# zeta2rework_lw_v7.net
KiCad netlist of a schematic drawn in EAGLE
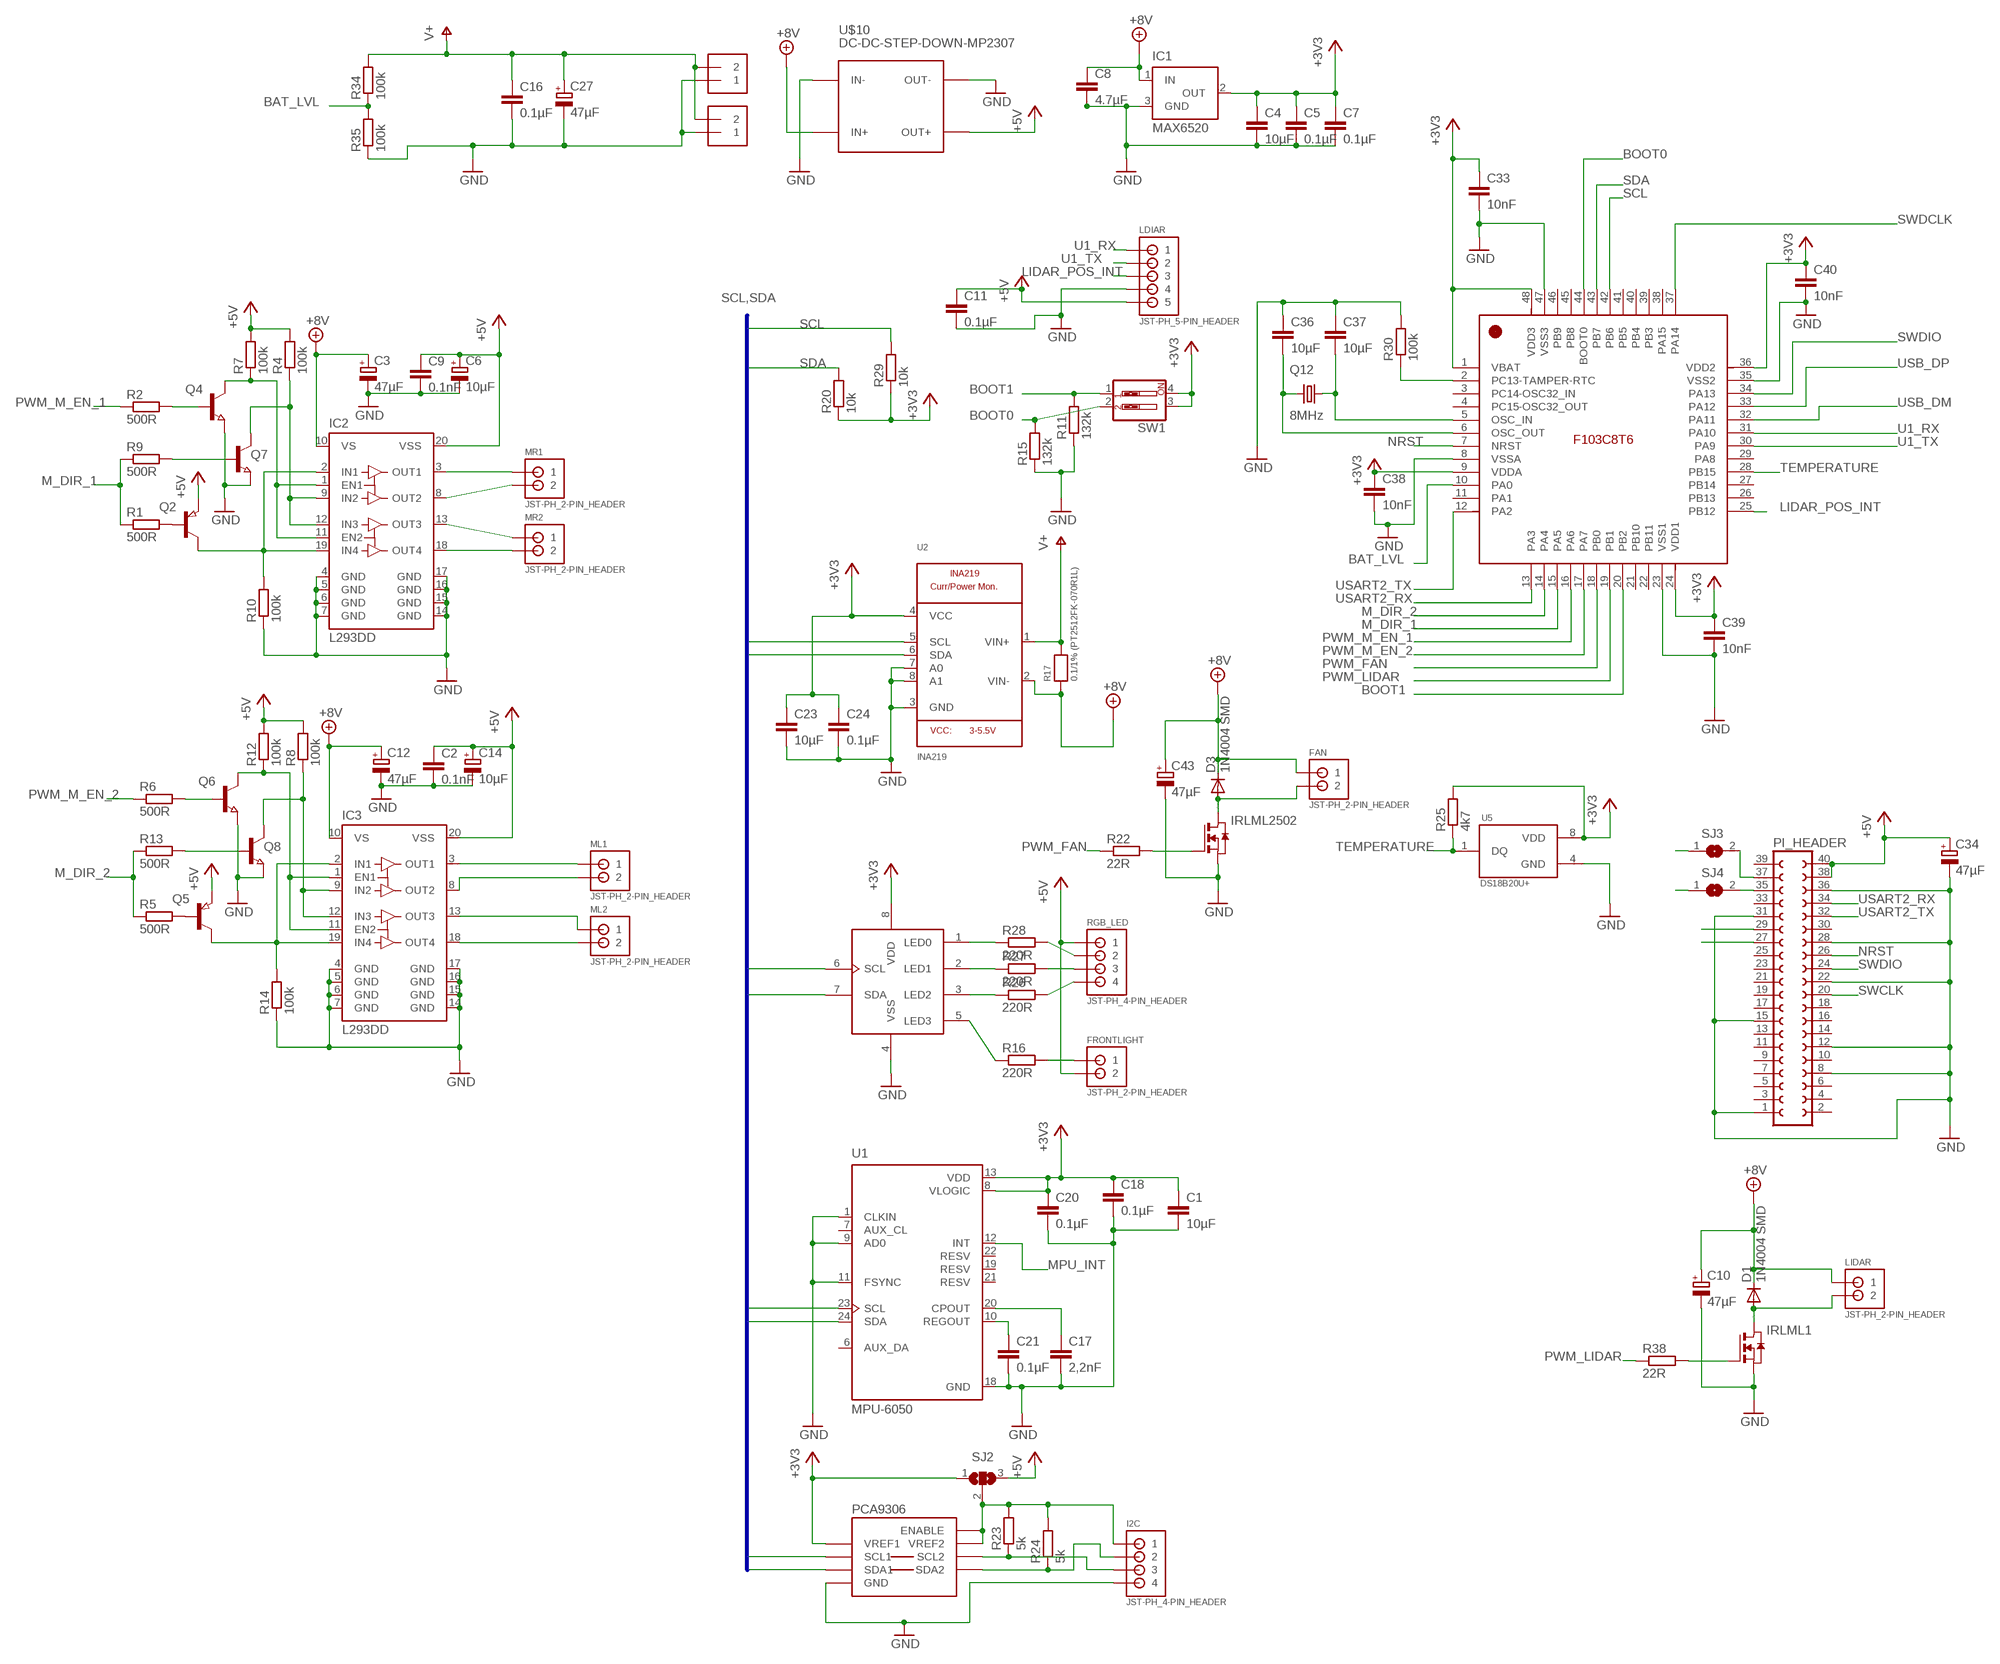
[diagram p0: schematic, sheet 1]

(export (version "E")
  (design (tool "Eeschema 10.0.6"))
  (components
    (comp (ref "C1")
      (value "10µF")
      (footprint "eagle-import:C1206")
      (libsource (lib "eagle-import") (part "C-EUC1206"))
    )
    (comp (ref "C2")
      (value "0.1nF")
      (footprint "eagle-import:C1206")
      (libsource (lib "eagle-import") (part "C-EUC1206"))
    )
    (comp (ref "C3")
      (value "47µF")
      (footprint "eagle-import:UD-4X5,8_NICHICON")
      (libsource (lib "eagle-import") (part "CPOL-EUUD-4X5,8"))
    )
    (comp (ref "C4")
      (value "10µF")
      (footprint "eagle-import:C1206")
      (libsource (lib "eagle-import") (part "C-EUC1206"))
    )
    (comp (ref "C5")
      (value "0.1µF")
      (footprint "eagle-import:C1206")
      (libsource (lib "eagle-import") (part "C-EUC1206"))
    )
    (comp (ref "C6")
      (value "10µF")
      (footprint "eagle-import:UD-4X5,8_NICHICON")
      (libsource (lib "eagle-import") (part "CPOL-EUUD-4X5,8"))
    )
    (comp (ref "C7")
      (value "0.1µF")
      (footprint "eagle-import:C1206")
      (libsource (lib "eagle-import") (part "C-EUC1206"))
    )
    (comp (ref "C8")
      (value "4.7µF")
      (footprint "eagle-import:C1206")
      (libsource (lib "eagle-import") (part "C-EUC1206"))
    )
    (comp (ref "C9")
      (value "0.1nF")
      (footprint "eagle-import:C1206")
      (libsource (lib "eagle-import") (part "C-EUC1206"))
    )
    (comp (ref "C10")
      (value "47µF")
      (footprint "eagle-import:UD-4X5,8_NICHICON")
      (libsource (lib "eagle-import") (part "CPOL-EUUD-4X5,8"))
    )
    (comp (ref "C11")
      (value "0.1µF")
      (footprint "eagle-import:C1206")
      (libsource (lib "eagle-import") (part "C-EUC1206"))
    )
    (comp (ref "C12")
      (value "47µF")
      (footprint "eagle-import:UD-4X5,8_NICHICON")
      (libsource (lib "eagle-import") (part "CPOL-EUUD-4X5,8"))
    )
    (comp (ref "C14")
      (value "10µF")
      (footprint "eagle-import:UD-4X5,8_NICHICON")
      (libsource (lib "eagle-import") (part "CPOL-EUUD-4X5,8"))
    )
    (comp (ref "C16")
      (value "0.1µF")
      (footprint "eagle-import:C1206")
      (libsource (lib "eagle-import") (part "C-EUC1206"))
    )
    (comp (ref "C17")
      (value "2,2nF")
      (footprint "eagle-import:C1206")
      (libsource (lib "eagle-import") (part "C-EUC1206"))
    )
    (comp (ref "C18")
      (value "0.1µF")
      (footprint "eagle-import:C1206")
      (libsource (lib "eagle-import") (part "C-EUC1206"))
    )
    (comp (ref "C20")
      (value "0.1µF")
      (footprint "eagle-import:C1206")
      (libsource (lib "eagle-import") (part "C-EUC1206"))
    )
    (comp (ref "C21")
      (value "0.1µF")
      (footprint "eagle-import:C1206")
      (libsource (lib "eagle-import") (part "C-EUC1206"))
    )
    (comp (ref "C23")
      (value "10µF")
      (footprint "eagle-import:C1206")
      (libsource (lib "eagle-import") (part "C-EUC1206"))
    )
    (comp (ref "C24")
      (value "0.1µF")
      (footprint "eagle-import:C1206")
      (libsource (lib "eagle-import") (part "C-EUC1206"))
    )
    (comp (ref "C27")
      (value "47µF")
      (footprint "eagle-import:UD-4X5,8_NICHICON")
      (libsource (lib "eagle-import") (part "CPOL-EUUD-4X5,8"))
    )
    (comp (ref "C33")
      (value "10nF")
      (footprint "eagle-import:C1206")
      (libsource (lib "eagle-import") (part "C-EUC1206"))
    )
    (comp (ref "C34")
      (value "47µF")
      (footprint "eagle-import:UD-4X5,8_NICHICON")
      (libsource (lib "eagle-import") (part "CPOL-EUUD-4X5,8"))
    )
    (comp (ref "C36")
      (value "10µF")
      (footprint "eagle-import:C1206")
      (libsource (lib "eagle-import") (part "C-EUC1206"))
    )
    (comp (ref "C37")
      (value "10µF")
      (footprint "eagle-import:C1206")
      (libsource (lib "eagle-import") (part "C-EUC1206"))
    )
    (comp (ref "C38")
      (value "10nF")
      (footprint "eagle-import:C1206")
      (libsource (lib "eagle-import") (part "C-EUC1206"))
    )
    (comp (ref "C39")
      (value "10nF")
      (footprint "eagle-import:C1206")
      (libsource (lib "eagle-import") (part "C-EUC1206"))
    )
    (comp (ref "C40")
      (value "10nF")
      (footprint "eagle-import:C1206")
      (libsource (lib "eagle-import") (part "C-EUC1206"))
    )
    (comp (ref "C43")
      (value "47µF")
      (footprint "eagle-import:UD-4X5,8_NICHICON")
      (libsource (lib "eagle-import") (part "CPOL-EUUD-4X5,8"))
    )
    (comp (ref "D1")
      (value "1N4004 SMD")
      (footprint "eagle-import:DO214AC")
      (libsource (lib "eagle-import") (part "DIODE-DO214AC"))
    )
    (comp (ref "D3")
      (value "1N4004 SMD")
      (footprint "eagle-import:DO214AC")
      (libsource (lib "eagle-import") (part "DIODE-DO214AC"))
    )
    (comp (ref "FAN")
      (value "JST-PH_2-PIN_HEADER")
      (footprint "eagle-import:JST_B2B-PH_HEADER")
      (libsource (lib "eagle-import") (part "JST-PH_2-PIN_HEADER"))
    )
    (comp (ref "FRONTLIGHT")
      (value "JST-PH_2-PIN_HEADER")
      (footprint "eagle-import:JST_B2B-PH_HEADER")
      (libsource (lib "eagle-import") (part "JST-PH_2-PIN_HEADER"))
    )
    (comp (ref "I2C")
      (value "JST-PH_4-PIN_HEADER")
      (footprint "eagle-import:JST_B4B-PH_HEADER")
      (libsource (lib "eagle-import") (part "JST-PH_4-PIN_HEADER"))
    )
    (comp (ref "IC1")
      (value "MAX6520")
      (footprint "eagle-import:SOT23")
      (fields (field (name "MF") "MAXIM") (field (name "MPN") "MAX6520EUR-T"))
      (libsource (lib "eagle-import") (part "MAX6520"))
    )
    (comp (ref "IC2")
      (value "L293DD")
      (footprint "eagle-import:SO20")
      (libsource (lib "eagle-import") (part "L293DD"))
    )
    (comp (ref "IC3")
      (value "L293DD")
      (footprint "eagle-import:SO20")
      (libsource (lib "eagle-import") (part "L293DD"))
    )
    (comp (ref "IRLML1")
      (value "NMOSSOT23")
      (footprint "eagle-import:SOT-23")
      (libsource (lib "eagle-import") (part "NMOSSOT23"))
    )
    (comp (ref "IRLML2502")
      (value "NMOSSOT23")
      (footprint "eagle-import:SOT-23")
      (libsource (lib "eagle-import") (part "NMOSSOT23"))
    )
    (comp (ref "LDIAR")
      (value "JST-PH_5-PIN_HEADER")
      (footprint "eagle-import:JST_B5B-PH_HEADER")
      (libsource (lib "eagle-import") (part "JST-PH_5-PIN_HEADER"))
    )
    (comp (ref "LIDAR")
      (value "JST-PH_2-PIN_HEADER")
      (footprint "eagle-import:JST_B2B-PH_HEADER")
      (libsource (lib "eagle-import") (part "JST-PH_2-PIN_HEADER"))
    )
    (comp (ref "ML1")
      (value "JST-PH_2-PIN_HEADER")
      (footprint "eagle-import:JST_B2B-PH_HEADER")
      (libsource (lib "eagle-import") (part "JST-PH_2-PIN_HEADER"))
    )
    (comp (ref "ML2")
      (value "JST-PH_2-PIN_HEADER")
      (footprint "eagle-import:JST_B2B-PH_HEADER")
      (libsource (lib "eagle-import") (part "JST-PH_2-PIN_HEADER"))
    )
    (comp (ref "MR1")
      (value "JST-PH_2-PIN_HEADER")
      (footprint "eagle-import:JST_B2B-PH_HEADER")
      (libsource (lib "eagle-import") (part "JST-PH_2-PIN_HEADER"))
    )
    (comp (ref "MR2")
      (value "JST-PH_2-PIN_HEADER")
      (footprint "eagle-import:JST_B2B-PH_HEADER")
      (libsource (lib "eagle-import") (part "JST-PH_2-PIN_HEADER"))
    )
    (comp (ref "PCA9306")
      (value "IC2_LEVEL_TRANSLATER")
      (footprint "eagle-import:SOIC-8")
      (libsource (lib "eagle-import") (part "IC2_LEVEL_TRANSLATER"))
    )
    (comp (ref "PCA9533")
      (value "PCA9533")
      (footprint "eagle-import:SOIC8")
      (libsource (lib "eagle-import") (part "PCA9533"))
    )
    (comp (ref "PI_HEADER")
      (value "FE20-2")
      (footprint "eagle-import:FE20-2")
      (libsource (lib "eagle-import") (part "FE20-2"))
    )
    (comp (ref "Q2")
      (value "PNP-TRANSISTOR_SOT23")
      (footprint "eagle-import:SOT23")
      (libsource (lib "eagle-import") (part "PNP-TRANSISTOR_SOT23"))
    )
    (comp (ref "Q4")
      (value "NPN-TRANSISTOR_SOT23")
      (footprint "eagle-import:SOT23")
      (libsource (lib "eagle-import") (part "NPN-TRANSISTOR_SOT23"))
    )
    (comp (ref "Q5")
      (value "PNP-TRANSISTOR_SOT23")
      (footprint "eagle-import:SOT23")
      (libsource (lib "eagle-import") (part "PNP-TRANSISTOR_SOT23"))
    )
    (comp (ref "Q6")
      (value "NPN-TRANSISTOR_SOT23")
      (footprint "eagle-import:SOT23")
      (libsource (lib "eagle-import") (part "NPN-TRANSISTOR_SOT23"))
    )
    (comp (ref "Q7")
      (value "NPN-TRANSISTOR_SOT23")
      (footprint "eagle-import:SOT23")
      (libsource (lib "eagle-import") (part "NPN-TRANSISTOR_SOT23"))
    )
    (comp (ref "Q8")
      (value "NPN-TRANSISTOR_SOT23")
      (footprint "eagle-import:SOT23")
      (libsource (lib "eagle-import") (part "NPN-TRANSISTOR_SOT23"))
    )
    (comp (ref "Q12")
      (value "8MHz")
      (footprint "eagle-import:7.0X5.0")
      (libsource (lib "eagle-import") (part "KX-13"))
    )
    (comp (ref "R1")
      (value "500R")
      (footprint "eagle-import:R0603")
      (libsource (lib "eagle-import") (part "R-EU_R0603"))
    )
    (comp (ref "R2")
      (value "500R")
      (footprint "eagle-import:R0603")
      (libsource (lib "eagle-import") (part "R-EU_R0603"))
    )
    (comp (ref "R4")
      (value "100k")
      (footprint "eagle-import:R0603")
      (libsource (lib "eagle-import") (part "R-EU_R0603"))
    )
    (comp (ref "R5")
      (value "500R")
      (footprint "eagle-import:R0603")
      (libsource (lib "eagle-import") (part "R-EU_R0603"))
    )
    (comp (ref "R6")
      (value "500R")
      (footprint "eagle-import:R0603")
      (libsource (lib "eagle-import") (part "R-EU_R0603"))
    )
    (comp (ref "R7")
      (value "100k")
      (footprint "eagle-import:R0603")
      (libsource (lib "eagle-import") (part "R-EU_R0603"))
    )
    (comp (ref "R8")
      (value "100k")
      (footprint "eagle-import:R0603")
      (libsource (lib "eagle-import") (part "R-EU_R0603"))
    )
    (comp (ref "R9")
      (value "500R")
      (footprint "eagle-import:R0603")
      (libsource (lib "eagle-import") (part "R-EU_R0603"))
    )
    (comp (ref "R10")
      (value "100k")
      (footprint "eagle-import:R0603")
      (libsource (lib "eagle-import") (part "R-EU_R0603"))
    )
    (comp (ref "R11")
      (value "132k")
      (footprint "eagle-import:R0603")
      (libsource (lib "eagle-import") (part "R-EU_R0603"))
    )
    (comp (ref "R12")
      (value "100k")
      (footprint "eagle-import:R0603")
      (libsource (lib "eagle-import") (part "R-EU_R0603"))
    )
    (comp (ref "R13")
      (value "500R")
      (footprint "eagle-import:R0603")
      (libsource (lib "eagle-import") (part "R-EU_R0603"))
    )
    (comp (ref "R14")
      (value "100k")
      (footprint "eagle-import:R0603")
      (libsource (lib "eagle-import") (part "R-EU_R0603"))
    )
    (comp (ref "R15")
      (value "132k")
      (footprint "eagle-import:R0603")
      (libsource (lib "eagle-import") (part "R-EU_R0603"))
    )
    (comp (ref "R16")
      (value "220R")
      (footprint "eagle-import:R0603")
      (libsource (lib "eagle-import") (part "R-EU_R0603"))
    )
    (comp (ref "R17")
      (value "0.1/1% (PT2512FK-070R1L)")
      (footprint "eagle-import:2512")
      (libsource (lib "eagle-import") (part "RESISTOR2512"))
    )
    (comp (ref "R20")
      (value "10k")
      (footprint "eagle-import:R0603")
      (libsource (lib "eagle-import") (part "R-EU_R0603"))
    )
    (comp (ref "R22")
      (value "22R")
      (footprint "eagle-import:R0603")
      (libsource (lib "eagle-import") (part "R-EU_R0603"))
    )
    (comp (ref "R23")
      (value "5k")
      (footprint "eagle-import:R0603")
      (libsource (lib "eagle-import") (part "R-EU_R0603"))
    )
    (comp (ref "R24")
      (value "5k")
      (footprint "eagle-import:R0603")
      (libsource (lib "eagle-import") (part "R-EU_R0603"))
    )
    (comp (ref "R25")
      (value "4k7")
      (footprint "eagle-import:R0603")
      (libsource (lib "eagle-import") (part "R-EU_R0603"))
    )
    (comp (ref "R26")
      (value "220R")
      (footprint "eagle-import:R0603")
      (libsource (lib "eagle-import") (part "R-EU_R0603"))
    )
    (comp (ref "R27")
      (value "220R")
      (footprint "eagle-import:R0603")
      (libsource (lib "eagle-import") (part "R-EU_R0603"))
    )
    (comp (ref "R28")
      (value "220R")
      (footprint "eagle-import:R0603")
      (libsource (lib "eagle-import") (part "R-EU_R0603"))
    )
    (comp (ref "R29")
      (value "10k")
      (footprint "eagle-import:R0603")
      (libsource (lib "eagle-import") (part "R-EU_R0603"))
    )
    (comp (ref "R30")
      (value "100k")
      (footprint "eagle-import:R0603")
      (libsource (lib "eagle-import") (part "R-EU_R0603"))
    )
    (comp (ref "R34")
      (value "100k")
      (footprint "eagle-import:R0603")
      (libsource (lib "eagle-import") (part "R-EU_R0603"))
    )
    (comp (ref "R35")
      (value "100k")
      (footprint "eagle-import:R0603")
      (libsource (lib "eagle-import") (part "R-EU_R0603"))
    )
    (comp (ref "R38")
      (value "22R")
      (footprint "eagle-import:R0603")
      (libsource (lib "eagle-import") (part "R-EU_R0603"))
    )
    (comp (ref "RGB_LED")
      (value "JST-PH_4-PIN_HEADER")
      (footprint "eagle-import:JST_B4B-PH_HEADER")
      (libsource (lib "eagle-import") (part "JST-PH_4-PIN_HEADER"))
    )
    (comp (ref "SJ2")
      (value "SJ2W")
      (footprint "eagle-import:SJ_2")
      (libsource (lib "eagle-import") (part "SJ2W"))
    )
    (comp (ref "SJ3")
      (value "SOLDERJUMPERREFLOW_NOPASTE")
      (footprint "eagle-import:SOLDERJUMPER_REFLOW_NOPASTE")
      (libsource (lib "eagle-import") (part "SOLDERJUMPERREFLOW_NOPASTE"))
    )
    (comp (ref "SJ4")
      (value "SOLDERJUMPERREFLOW_NOPASTE")
      (footprint "eagle-import:SOLDERJUMPER_REFLOW_NOPASTE")
      (libsource (lib "eagle-import") (part "SOLDERJUMPERREFLOW_NOPASTE"))
    )
    (comp (ref "STM32F103CB")
      (value "STM32F103CB")
      (footprint "eagle-import:LQFP48_7X7MM_0.5MMPP")
      (fields (field (name "MF") "STMicroelectronics") (field (name "MP") "STM32F103C8T6"))
      (libsource (lib "eagle-import") (part "STM32F103C8T6"))
    )
    (comp (ref "SUPPLY_IN")
      (value "TERMBLOCK_1X2-3.5MM")
      (footprint "eagle-import:1X2-3.5MM")
      (libsource (lib "eagle-import") (part "TERMBLOCK_1X2-3.5MM"))
    )
    (comp (ref "SUPPLY_IN1")
      (value "TERMBLOCK_1X2-3.5MM")
      (footprint "eagle-import:1X2-3.5MM")
      (libsource (lib "eagle-import") (part "TERMBLOCK_1X2-3.5MM"))
    )
    (comp (ref "SW1")
      (value "SW_DIP-2")
      (footprint "eagle-import:EDG-02")
      (libsource (lib "eagle-import") (part "SW_DIP-2"))
    )
    (comp (ref "U$10")
      (value "DC-DC-STEP-DOWN-MP2307")
      (footprint "eagle-import:DC-DC-STEP-DOWN-MP2307")
      (libsource (lib "eagle-import") (part "DC-DC-STEP-DOWN-MP2307"))
    )
    (comp (ref "U1")
      (value "MPU-6050")
      (footprint "eagle-import:QFN50P400X400X95-24N")
      (fields (field (name "MF") "TDK"))
      (libsource (lib "eagle-import") (part "MPU-6050"))
    )
    (comp (ref "U2")
      (value "INA219")
      (footprint "eagle-import:SOT23-8")
      (fields (field (name "MF") "Texas Instruments"))
      (libsource (lib "eagle-import") (part "INA219"))
    )
    (comp (ref "U5")
      (value "DS18B20U+")
      (footprint "eagle-import:SOP65P490X95-8N")
      (fields (field (name "MF") "Maxim"))
      (libsource (lib "eagle-import") (part "DS18B20U+"))
    )
  )
  (nets
    (net (code "1") (name "+3V3") (class "Default")
      (node (ref "C1") (pin "1") (pinfunction "1_1") (pintype "passive"))
      (node (ref "C18") (pin "1") (pinfunction "1_1") (pintype "passive"))
      (node (ref "C20") (pin "1") (pinfunction "1_1") (pintype "passive"))
      (node (ref "C23") (pin "1") (pinfunction "1_1") (pintype "passive"))
      (node (ref "C24") (pin "1") (pinfunction "1_1") (pintype "passive"))
      (node (ref "C33") (pin "1") (pinfunction "1_1") (pintype "passive"))
      (node (ref "C38") (pin "1") (pinfunction "1_1") (pintype "passive"))
      (node (ref "C39") (pin "1") (pinfunction "1_1") (pintype "passive"))
      (node (ref "C4") (pin "1") (pinfunction "1_1") (pintype "passive"))
      (node (ref "C40") (pin "1") (pinfunction "1_1") (pintype "passive"))
      (node (ref "C5") (pin "1") (pinfunction "1_1") (pintype "passive"))
      (node (ref "C7") (pin "1") (pinfunction "1_1") (pintype "passive"))
      (node (ref "IC1") (pin "2") (pinfunction "OUT_2") (pintype "output"))
      (node (ref "PCA9306") (pin "1") (pinfunction "VREF1_1") (pintype "power_in"))
      (node (ref "PCA9533") (pin "8") (pinfunction "VDD_8") (pintype "power_in"))
      (node (ref "R20") (pin "1") (pinfunction "1_1") (pintype "passive"))
      (node (ref "R25") (pin "2") (pinfunction "2_2") (pintype "passive"))
      (node (ref "R29") (pin "1") (pinfunction "1_1") (pintype "passive"))
      (node (ref "SJ2") (pin "1") (pinfunction "1_1") (pintype "passive"))
      (node (ref "STM32F103CB") (pin "1") (pinfunction "VBAT_1") (pintype "bidirectional"))
      (node (ref "STM32F103CB") (pin "24") (pinfunction "VDD1_24") (pintype "bidirectional"))
      (node (ref "STM32F103CB") (pin "36") (pinfunction "VDD2_36") (pintype "bidirectional"))
      (node (ref "STM32F103CB") (pin "48") (pinfunction "VDD3_48") (pintype "bidirectional"))
      (node (ref "STM32F103CB") (pin "9") (pinfunction "VDDA_9") (pintype "bidirectional"))
      (node (ref "SW1") (pin "3") (pinfunction "3_3") (pintype "passive"))
      (node (ref "SW1") (pin "4") (pinfunction "4_4") (pintype "passive"))
      (node (ref "U1") (pin "13") (pinfunction "VDD_13") (pintype "power_in"))
      (node (ref "U1") (pin "8") (pinfunction "VLOGIC_8") (pintype "power_in"))
      (node (ref "U2") (pin "4") (pinfunction "VCC_4") (pintype "bidirectional"))
      (node (ref "U5") (pin "8") (pinfunction "VDD_8") (pintype "power_in"))
    )
    (net (code "2") (name "+5V") (class "Default")
      (node (ref "C11") (pin "1") (pinfunction "1_1") (pintype "passive"))
      (node (ref "C14") (pin "+") (pinfunction "+_+") (pintype "passive"))
      (node (ref "C2") (pin "1") (pinfunction "1_1") (pintype "passive"))
      (node (ref "C34") (pin "+") (pinfunction "+_+") (pintype "passive"))
      (node (ref "C6") (pin "+") (pinfunction "+_+") (pintype "passive"))
      (node (ref "C9") (pin "1") (pinfunction "1_1") (pintype "passive"))
      (node (ref "FRONTLIGHT") (pin "P2") (pinfunction "2_P2") (pintype "bidirectional"))
      (node (ref "IC2") (pin "20") (pinfunction "VSS_20") (pintype "power_in"))
      (node (ref "IC3") (pin "20") (pinfunction "VSS_20") (pintype "power_in"))
      (node (ref "LDIAR") (pin "P5") (pinfunction "5_P5") (pintype "bidirectional"))
      (node (ref "PI_HEADER") (pin "38") (pinfunction "38_38") (pintype "passive"))
      (node (ref "PI_HEADER") (pin "40") (pinfunction "40_40") (pintype "passive"))
      (node (ref "Q2") (pin "2") (pinfunction "E_2") (pintype "passive"))
      (node (ref "Q5") (pin "2") (pinfunction "E_2") (pintype "passive"))
      (node (ref "R12") (pin "2") (pinfunction "2_2") (pintype "passive"))
      (node (ref "R4") (pin "2") (pinfunction "2_2") (pintype "passive"))
      (node (ref "R7") (pin "2") (pinfunction "2_2") (pintype "passive"))
      (node (ref "R8") (pin "2") (pinfunction "2_2") (pintype "passive"))
      (node (ref "RGB_LED") (pin "P1") (pinfunction "1_P1") (pintype "bidirectional"))
      (node (ref "SJ2") (pin "3") (pinfunction "3_3") (pintype "passive"))
      (node (ref "U$10") (pin "OUT+") (pinfunction "OUT+_OUT+") (pintype "bidirectional"))
    )
    (net (code "3") (name "+8V") (class "Default")
      (node (ref "C10") (pin "+") (pinfunction "+_+") (pintype "passive"))
      (node (ref "C12") (pin "+") (pinfunction "+_+") (pintype "passive"))
      (node (ref "C3") (pin "+") (pinfunction "+_+") (pintype "passive"))
      (node (ref "C43") (pin "+") (pinfunction "+_+") (pintype "passive"))
      (node (ref "C8") (pin "1") (pinfunction "1_1") (pintype "passive"))
      (node (ref "D1") (pin "C") (pinfunction "C_C") (pintype "passive"))
      (node (ref "D3") (pin "C") (pinfunction "C_C") (pintype "passive"))
      (node (ref "FAN") (pin "P1") (pinfunction "1_P1") (pintype "bidirectional"))
      (node (ref "IC1") (pin "1") (pinfunction "IN_1") (pintype "input"))
      (node (ref "IC2") (pin "10") (pinfunction "VS_10") (pintype "power_in"))
      (node (ref "IC3") (pin "10") (pinfunction "VS_10") (pintype "power_in"))
      (node (ref "LIDAR") (pin "P1") (pinfunction "1_P1") (pintype "bidirectional"))
      (node (ref "R17") (pin "1") (pinfunction "1_1") (pintype "passive"))
      (node (ref "U$10") (pin "IN+") (pinfunction "IN+_IN+") (pintype "bidirectional"))
      (node (ref "U2") (pin "2") (pinfunction "VIN-_2") (pintype "bidirectional"))
    )
    (net (code "4") (name "/BAT_LVL") (class "Default")
      (node (ref "R34") (pin "1") (pinfunction "1_1") (pintype "passive"))
      (node (ref "R35") (pin "2") (pinfunction "2_2") (pintype "passive"))
      (node (ref "STM32F103CB") (pin "10") (pinfunction "PA0_10") (pintype "bidirectional"))
    )
    (net (code "5") (name "/BOOT0") (class "Default")
      (node (ref "R15") (pin "2") (pinfunction "2_2") (pintype "passive"))
      (node (ref "STM32F103CB") (pin "44") (pinfunction "BOOT0_44") (pintype "bidirectional"))
      (node (ref "SW1") (pin "2") (pinfunction "2_2") (pintype "passive"))
    )
    (net (code "6") (name "/BOOT1") (class "Default")
      (node (ref "R11") (pin "2") (pinfunction "2_2") (pintype "passive"))
      (node (ref "STM32F103CB") (pin "20") (pinfunction "PB2_20") (pintype "bidirectional"))
      (node (ref "SW1") (pin "1") (pinfunction "1_1") (pintype "passive"))
    )
    (net (code "7") (name "/LIDAR_POS_INT") (class "Default")
      (node (ref "LDIAR") (pin "P3") (pinfunction "3_P3") (pintype "bidirectional"))
      (node (ref "STM32F103CB") (pin "25") (pinfunction "PB12_25") (pintype "bidirectional"))
    )
    (net (code "8") (name "/MPU_INT") (class "Default")
      (node (ref "U1") (pin "12") (pinfunction "INT_12") (pintype "output"))
    )
    (net (code "9") (name "/M_DIR_1") (class "Default")
      (node (ref "R1") (pin "1") (pinfunction "1_1") (pintype "passive"))
      (node (ref "R9") (pin "1") (pinfunction "1_1") (pintype "passive"))
      (node (ref "STM32F103CB") (pin "15") (pinfunction "PA5_15") (pintype "bidirectional"))
    )
    (net (code "10") (name "/M_DIR_2") (class "Default")
      (node (ref "R13") (pin "1") (pinfunction "1_1") (pintype "passive"))
      (node (ref "R5") (pin "1") (pinfunction "1_1") (pintype "passive"))
      (node (ref "STM32F103CB") (pin "14") (pinfunction "PA4_14") (pintype "bidirectional"))
    )
    (net (code "11") (name "/NRST") (class "Default")
      (node (ref "PI_HEADER") (pin "26") (pinfunction "26_26") (pintype "passive"))
      (node (ref "STM32F103CB") (pin "7") (pinfunction "NRST_7") (pintype "bidirectional"))
    )
    (net (code "12") (name "/PWM_FAN") (class "Default")
      (node (ref "R22") (pin "1") (pinfunction "1_1") (pintype "passive"))
      (node (ref "STM32F103CB") (pin "18") (pinfunction "PB0_18") (pintype "bidirectional"))
    )
    (net (code "13") (name "/PWM_LIDAR") (class "Default")
      (node (ref "R38") (pin "1") (pinfunction "1_1") (pintype "passive"))
      (node (ref "STM32F103CB") (pin "19") (pinfunction "PB1_19") (pintype "bidirectional"))
    )
    (net (code "14") (name "/PWM_M_EN_1") (class "Default")
      (node (ref "R2") (pin "1") (pinfunction "1_1") (pintype "passive"))
      (node (ref "STM32F103CB") (pin "16") (pinfunction "PA6_16") (pintype "bidirectional"))
    )
    (net (code "15") (name "/PWM_M_EN_2") (class "Default")
      (node (ref "R6") (pin "1") (pinfunction "1_1") (pintype "passive"))
      (node (ref "STM32F103CB") (pin "17") (pinfunction "PA7_17") (pintype "bidirectional"))
    )
    (net (code "16") (name "/SCL") (class "Default")
      (node (ref "PCA9533") (pin "6") (pinfunction "SCL_6") (pintype "input"))
      (node (ref "R29") (pin "2") (pinfunction "2_2") (pintype "passive"))
      (node (ref "STM32F103CB") (pin "42") (pinfunction "PB6_42") (pintype "bidirectional"))
      (node (ref "U1") (pin "23") (pinfunction "SCL_23") (pintype "input"))
      (node (ref "U2") (pin "5") (pinfunction "SCL_5") (pintype "bidirectional"))
    )
    (net (code "17") (name "/SDA") (class "Default")
      (node (ref "PCA9533") (pin "7") (pinfunction "SDA_7") (pintype "bidirectional"))
      (node (ref "R20") (pin "2") (pinfunction "2_2") (pintype "passive"))
      (node (ref "STM32F103CB") (pin "43") (pinfunction "PB7_43") (pintype "bidirectional"))
      (node (ref "U1") (pin "24") (pinfunction "SDA_24") (pintype "bidirectional"))
      (node (ref "U2") (pin "6") (pinfunction "SDA_6") (pintype "bidirectional"))
    )
    (net (code "18") (name "/SWCLK") (class "Default")
      (node (ref "PI_HEADER") (pin "20") (pinfunction "20_20") (pintype "passive"))
    )
    (net (code "19") (name "/SWDCLK") (class "Default")
      (node (ref "STM32F103CB") (pin "37") (pinfunction "PA14_37") (pintype "bidirectional"))
    )
    (net (code "20") (name "/SWDIO") (class "Default")
      (node (ref "PI_HEADER") (pin "24") (pinfunction "24_24") (pintype "passive"))
      (node (ref "STM32F103CB") (pin "34") (pinfunction "PA13_34") (pintype "bidirectional"))
    )
    (net (code "21") (name "/TEMPERATURE") (class "Default")
      (node (ref "R25") (pin "1") (pinfunction "1_1") (pintype "passive"))
      (node (ref "STM32F103CB") (pin "28") (pinfunction "PB15_28") (pintype "bidirectional"))
      (node (ref "U5") (pin "1") (pinfunction "DQ_1") (pintype "bidirectional"))
    )
    (net (code "22") (name "/U1_RX") (class "Default")
      (node (ref "LDIAR") (pin "P1") (pinfunction "1_P1") (pintype "bidirectional"))
      (node (ref "STM32F103CB") (pin "31") (pinfunction "PA10_31") (pintype "bidirectional"))
    )
    (net (code "23") (name "/U1_TX") (class "Default")
      (node (ref "LDIAR") (pin "P2") (pinfunction "2_P2") (pintype "bidirectional"))
      (node (ref "STM32F103CB") (pin "30") (pinfunction "PA9_30") (pintype "bidirectional"))
    )
    (net (code "24") (name "/USART2_RX") (class "Default")
      (node (ref "PI_HEADER") (pin "34") (pinfunction "34_34") (pintype "passive"))
      (node (ref "STM32F103CB") (pin "13") (pinfunction "PA3_13") (pintype "bidirectional"))
    )
    (net (code "25") (name "/USART2_TX") (class "Default")
      (node (ref "PI_HEADER") (pin "32") (pinfunction "32_32") (pintype "passive"))
      (node (ref "STM32F103CB") (pin "12") (pinfunction "PA2_12") (pintype "bidirectional"))
    )
    (net (code "26") (name "/USB_DM") (class "Default")
      (node (ref "STM32F103CB") (pin "32") (pinfunction "PA11_32") (pintype "bidirectional"))
    )
    (net (code "27") (name "/USB_DP") (class "Default")
      (node (ref "STM32F103CB") (pin "33") (pinfunction "PA12_33") (pintype "bidirectional"))
    )
    (net (code "29") (name "GND") (class "Default")
      (node (ref "C1") (pin "2") (pinfunction "2_2") (pintype "passive"))
      (node (ref "C10") (pin "-") (pinfunction "-_-") (pintype "passive"))
      (node (ref "C11") (pin "2") (pinfunction "2_2") (pintype "passive"))
      (node (ref "C12") (pin "-") (pinfunction "-_-") (pintype "passive"))
      (node (ref "C14") (pin "-") (pinfunction "-_-") (pintype "passive"))
      (node (ref "C16") (pin "2") (pinfunction "2_2") (pintype "passive"))
      (node (ref "C17") (pin "2") (pinfunction "2_2") (pintype "passive"))
      (node (ref "C18") (pin "2") (pinfunction "2_2") (pintype "passive"))
      (node (ref "C2") (pin "2") (pinfunction "2_2") (pintype "passive"))
      (node (ref "C20") (pin "2") (pinfunction "2_2") (pintype "passive"))
      (node (ref "C21") (pin "2") (pinfunction "2_2") (pintype "passive"))
      (node (ref "C23") (pin "2") (pinfunction "2_2") (pintype "passive"))
      (node (ref "C24") (pin "2") (pinfunction "2_2") (pintype "passive"))
      (node (ref "C27") (pin "-") (pinfunction "-_-") (pintype "passive"))
      (node (ref "C3") (pin "-") (pinfunction "-_-") (pintype "passive"))
      (node (ref "C33") (pin "2") (pinfunction "2_2") (pintype "passive"))
      (node (ref "C34") (pin "-") (pinfunction "-_-") (pintype "passive"))
      (node (ref "C36") (pin "1") (pinfunction "1_1") (pintype "passive"))
      (node (ref "C37") (pin "1") (pinfunction "1_1") (pintype "passive"))
      (node (ref "C38") (pin "2") (pinfunction "2_2") (pintype "passive"))
      (node (ref "C39") (pin "2") (pinfunction "2_2") (pintype "passive"))
      (node (ref "C4") (pin "2") (pinfunction "2_2") (pintype "passive"))
      (node (ref "C40") (pin "2") (pinfunction "2_2") (pintype "passive"))
      (node (ref "C43") (pin "-") (pinfunction "-_-") (pintype "passive"))
      (node (ref "C5") (pin "2") (pinfunction "2_2") (pintype "passive"))
      (node (ref "C6") (pin "-") (pinfunction "-_-") (pintype "passive"))
      (node (ref "C7") (pin "2") (pinfunction "2_2") (pintype "passive"))
      (node (ref "C8") (pin "2") (pinfunction "2_2") (pintype "passive"))
      (node (ref "C9") (pin "2") (pinfunction "2_2") (pintype "passive"))
      (node (ref "I2C") (pin "P4") (pinfunction "4_P4") (pintype "bidirectional"))
      (node (ref "IC1") (pin "3") (pinfunction "GND_3") (pintype "power_in"))
      (node (ref "IC2") (pin "14") (pinfunction "GND_14") (pintype "power_in"))
      (node (ref "IC2") (pin "15") (pinfunction "GND_15") (pintype "power_in"))
      (node (ref "IC2") (pin "16") (pinfunction "GND_16") (pintype "power_in"))
      (node (ref "IC2") (pin "17") (pinfunction "GND_17") (pintype "power_in"))
      (node (ref "IC2") (pin "4") (pinfunction "GND_4") (pintype "power_in"))
      (node (ref "IC2") (pin "5") (pinfunction "GND_5") (pintype "power_in"))
      (node (ref "IC2") (pin "6") (pinfunction "GND_6") (pintype "power_in"))
      (node (ref "IC2") (pin "7") (pinfunction "GND_7") (pintype "power_in"))
      (node (ref "IC3") (pin "14") (pinfunction "GND_14") (pintype "power_in"))
      (node (ref "IC3") (pin "15") (pinfunction "GND_15") (pintype "power_in"))
      (node (ref "IC3") (pin "16") (pinfunction "GND_16") (pintype "power_in"))
      (node (ref "IC3") (pin "17") (pinfunction "GND_17") (pintype "power_in"))
      (node (ref "IC3") (pin "4") (pinfunction "GND_4") (pintype "power_in"))
      (node (ref "IC3") (pin "5") (pinfunction "GND_5") (pintype "power_in"))
      (node (ref "IC3") (pin "6") (pinfunction "GND_6") (pintype "power_in"))
      (node (ref "IC3") (pin "7") (pinfunction "GND_7") (pintype "power_in"))
      (node (ref "IRLML1") (pin "2") (pinfunction "S_2") (pintype "passive"))
      (node (ref "IRLML2502") (pin "2") (pinfunction "S_2") (pintype "passive"))
      (node (ref "LDIAR") (pin "P4") (pinfunction "4_P4") (pintype "bidirectional"))
      (node (ref "PCA9306") (pin "4") (pinfunction "GND_4") (pintype "power_in"))
      (node (ref "PCA9533") (pin "4") (pinfunction "VSS_4") (pintype "power_in"))
      (node (ref "PI_HEADER") (pin "1") (pinfunction "1_1") (pintype "passive"))
      (node (ref "PI_HEADER") (pin "12") (pinfunction "12_12") (pintype "passive"))
      (node (ref "PI_HEADER") (pin "15") (pinfunction "15_15") (pintype "passive"))
      (node (ref "PI_HEADER") (pin "22") (pinfunction "22_22") (pintype "passive"))
      (node (ref "PI_HEADER") (pin "28") (pinfunction "28_28") (pintype "passive"))
      (node (ref "PI_HEADER") (pin "31") (pinfunction "31_31") (pintype "passive"))
      (node (ref "PI_HEADER") (pin "36") (pinfunction "36_36") (pintype "passive"))
      (node (ref "PI_HEADER") (pin "8") (pinfunction "8_8") (pintype "passive"))
      (node (ref "Q4") (pin "2") (pinfunction "E_2") (pintype "passive"))
      (node (ref "Q6") (pin "2") (pinfunction "E_2") (pintype "passive"))
      (node (ref "Q7") (pin "2") (pinfunction "E_2") (pintype "passive"))
      (node (ref "Q8") (pin "2") (pinfunction "E_2") (pintype "passive"))
      (node (ref "R10") (pin "1") (pinfunction "1_1") (pintype "passive"))
      (node (ref "R11") (pin "1") (pinfunction "1_1") (pintype "passive"))
      (node (ref "R14") (pin "1") (pinfunction "1_1") (pintype "passive"))
      (node (ref "R15") (pin "1") (pinfunction "1_1") (pintype "passive"))
      (node (ref "R30") (pin "2") (pinfunction "2_2") (pintype "passive"))
      (node (ref "R35") (pin "1") (pinfunction "1_1") (pintype "passive"))
      (node (ref "STM32F103CB") (pin "23") (pinfunction "VSS1_23") (pintype "bidirectional"))
      (node (ref "STM32F103CB") (pin "35") (pinfunction "VSS2_35") (pintype "bidirectional"))
      (node (ref "STM32F103CB") (pin "47") (pinfunction "VSS3_47") (pintype "bidirectional"))
      (node (ref "STM32F103CB") (pin "8") (pinfunction "VSSA_8") (pintype "bidirectional"))
      (node (ref "SUPPLY_IN") (pin "1") (pinfunction "1_1") (pintype "passive"))
      (node (ref "SUPPLY_IN1") (pin "1") (pinfunction "1_1") (pintype "passive"))
      (node (ref "U$10") (pin "IN-") (pinfunction "IN-_IN-") (pintype "bidirectional"))
      (node (ref "U$10") (pin "OUT-") (pinfunction "OUT-_OUT-") (pintype "bidirectional"))
      (node (ref "U1") (pin "1") (pinfunction "CLKIN_1") (pintype "input"))
      (node (ref "U1") (pin "11") (pinfunction "FSYNC_11") (pintype "input"))
      (node (ref "U1") (pin "18") (pinfunction "GND_18") (pintype "power_in"))
      (node (ref "U1") (pin "9") (pinfunction "AD0_9") (pintype "input"))
      (node (ref "U2") (pin "3") (pinfunction "GND_3") (pintype "bidirectional"))
      (node (ref "U2") (pin "7") (pinfunction "A0_7") (pintype "bidirectional"))
      (node (ref "U2") (pin "8") (pinfunction "A1_8") (pintype "bidirectional"))
      (node (ref "U5") (pin "4") (pinfunction "GND_4") (pintype "power_in"))
    )
    (net (code "30") (name "Net-(FAN-2)") (class "Default")
      (node (ref "D3") (pin "A") (pinfunction "A_A") (pintype "passive"))
      (node (ref "FAN") (pin "P2") (pinfunction "2_P2") (pintype "bidirectional"))
      (node (ref "IRLML2502") (pin "1") (pinfunction "D_1") (pintype "passive"))
    )
    (net (code "31") (name "Net-(FRONTLIGHT-1)") (class "Default")
      (node (ref "FRONTLIGHT") (pin "P1") (pinfunction "1_P1") (pintype "bidirectional"))
      (node (ref "R16") (pin "2") (pinfunction "2_2") (pintype "passive"))
    )
    (net (code "32") (name "Net-(I2C-1)") (class "Default")
      (node (ref "I2C") (pin "P1") (pinfunction "1_P1") (pintype "bidirectional"))
      (node (ref "PCA9306") (pin "7") (pinfunction "VREF2_7") (pintype "power_in"))
      (node (ref "PCA9306") (pin "8") (pinfunction "ENABLE_8") (pintype "input"))
      (node (ref "R23") (pin "2") (pinfunction "2_2") (pintype "passive"))
      (node (ref "R24") (pin "2") (pinfunction "2_2") (pintype "passive"))
      (node (ref "SJ2") (pin "2") (pinfunction "2_2") (pintype "passive"))
    )
    (net (code "33") (name "Net-(I2C-2)") (class "Default")
      (node (ref "I2C") (pin "P2") (pinfunction "2_P2") (pintype "bidirectional"))
      (node (ref "PCA9306") (pin "5") (pinfunction "SDA2_5") (pintype "bidirectional"))
      (node (ref "R24") (pin "1") (pinfunction "1_1") (pintype "passive"))
    )
    (net (code "34") (name "Net-(I2C-3)") (class "Default")
      (node (ref "I2C") (pin "P3") (pinfunction "3_P3") (pintype "bidirectional"))
      (node (ref "PCA9306") (pin "6") (pinfunction "SCL2_6") (pintype "bidirectional"))
      (node (ref "R23") (pin "1") (pinfunction "1_1") (pintype "passive"))
    )
    (net (code "35") (name "Net-(IC2-EN1)") (class "Default")
      (node (ref "IC2") (pin "1") (pinfunction "EN1_1") (pintype "input"))
      (node (ref "IC2") (pin "11") (pinfunction "EN2_11") (pintype "input"))
      (node (ref "Q4") (pin "3") (pinfunction "C_3") (pintype "passive"))
      (node (ref "R7") (pin "1") (pinfunction "1_1") (pintype "passive"))
    )
    (net (code "36") (name "Net-(IC2-IN1)") (class "Default")
      (node (ref "IC2") (pin "19") (pinfunction "IN4_19") (pintype "input"))
      (node (ref "IC2") (pin "2") (pinfunction "IN1_2") (pintype "input"))
      (node (ref "Q2") (pin "3") (pinfunction "C_3") (pintype "passive"))
      (node (ref "R10") (pin "2") (pinfunction "2_2") (pintype "passive"))
    )
    (net (code "37") (name "Net-(IC2-IN2)") (class "Default")
      (node (ref "IC2") (pin "12") (pinfunction "IN3_12") (pintype "input"))
      (node (ref "IC2") (pin "9") (pinfunction "IN2_9") (pintype "input"))
      (node (ref "Q7") (pin "3") (pinfunction "C_3") (pintype "passive"))
      (node (ref "R4") (pin "1") (pinfunction "1_1") (pintype "passive"))
    )
    (net (code "38") (name "Net-(IC2-OUT1)") (class "Default")
      (node (ref "IC2") (pin "3") (pinfunction "OUT1_3") (pintype "output"))
      (node (ref "MR1") (pin "P1") (pinfunction "1_P1") (pintype "bidirectional"))
    )
    (net (code "39") (name "Net-(IC2-OUT2)") (class "Default")
      (node (ref "IC2") (pin "8") (pinfunction "OUT2_8") (pintype "output"))
      (node (ref "MR1") (pin "P2") (pinfunction "2_P2") (pintype "bidirectional"))
    )
    (net (code "40") (name "Net-(IC2-OUT3)") (class "Default")
      (node (ref "IC2") (pin "13") (pinfunction "OUT3_13") (pintype "output"))
      (node (ref "MR2") (pin "P1") (pinfunction "1_P1") (pintype "bidirectional"))
    )
    (net (code "41") (name "Net-(IC2-OUT4)") (class "Default")
      (node (ref "IC2") (pin "18") (pinfunction "OUT4_18") (pintype "output"))
      (node (ref "MR2") (pin "P2") (pinfunction "2_P2") (pintype "bidirectional"))
    )
    (net (code "42") (name "Net-(IC3-EN1)") (class "Default")
      (node (ref "IC3") (pin "1") (pinfunction "EN1_1") (pintype "input"))
      (node (ref "IC3") (pin "11") (pinfunction "EN2_11") (pintype "input"))
      (node (ref "Q6") (pin "3") (pinfunction "C_3") (pintype "passive"))
      (node (ref "R12") (pin "1") (pinfunction "1_1") (pintype "passive"))
    )
    (net (code "43") (name "Net-(IC3-IN1)") (class "Default")
      (node (ref "IC3") (pin "19") (pinfunction "IN4_19") (pintype "input"))
      (node (ref "IC3") (pin "2") (pinfunction "IN1_2") (pintype "input"))
      (node (ref "Q5") (pin "3") (pinfunction "C_3") (pintype "passive"))
      (node (ref "R14") (pin "2") (pinfunction "2_2") (pintype "passive"))
    )
    (net (code "44") (name "Net-(IC3-IN2)") (class "Default")
      (node (ref "IC3") (pin "12") (pinfunction "IN3_12") (pintype "input"))
      (node (ref "IC3") (pin "9") (pinfunction "IN2_9") (pintype "input"))
      (node (ref "Q8") (pin "3") (pinfunction "C_3") (pintype "passive"))
      (node (ref "R8") (pin "1") (pinfunction "1_1") (pintype "passive"))
    )
    (net (code "45") (name "Net-(IC3-OUT1)") (class "Default")
      (node (ref "IC3") (pin "3") (pinfunction "OUT1_3") (pintype "output"))
      (node (ref "ML1") (pin "P1") (pinfunction "1_P1") (pintype "bidirectional"))
    )
    (net (code "46") (name "Net-(IC3-OUT2)") (class "Default")
      (node (ref "IC3") (pin "8") (pinfunction "OUT2_8") (pintype "output"))
      (node (ref "ML1") (pin "P2") (pinfunction "2_P2") (pintype "bidirectional"))
    )
    (net (code "47") (name "Net-(IC3-OUT3)") (class "Default")
      (node (ref "IC3") (pin "13") (pinfunction "OUT3_13") (pintype "output"))
      (node (ref "ML2") (pin "P1") (pinfunction "1_P1") (pintype "bidirectional"))
    )
    (net (code "48") (name "Net-(IC3-OUT4)") (class "Default")
      (node (ref "IC3") (pin "18") (pinfunction "OUT4_18") (pintype "output"))
      (node (ref "ML2") (pin "P2") (pinfunction "2_P2") (pintype "bidirectional"))
    )
    (net (code "49") (name "Net-(IRLML1-D)") (class "Default")
      (node (ref "D1") (pin "A") (pinfunction "A_A") (pintype "passive"))
      (node (ref "IRLML1") (pin "1") (pinfunction "D_1") (pintype "passive"))
      (node (ref "LIDAR") (pin "P2") (pinfunction "2_P2") (pintype "bidirectional"))
    )
    (net (code "50") (name "Net-(IRLML1-G)") (class "Default")
      (node (ref "IRLML1") (pin "3") (pinfunction "G_3") (pintype "passive"))
      (node (ref "R38") (pin "2") (pinfunction "2_2") (pintype "passive"))
    )
    (net (code "51") (name "Net-(IRLML2502-G)") (class "Default")
      (node (ref "IRLML2502") (pin "3") (pinfunction "G_3") (pintype "passive"))
      (node (ref "R22") (pin "2") (pinfunction "2_2") (pintype "passive"))
    )
    (net (code "52") (name "Net-(PCA9533-LED0)") (class "Default")
      (node (ref "PCA9533") (pin "1") (pinfunction "LED0_1") (pintype "bidirectional"))
      (node (ref "R28") (pin "1") (pinfunction "1_1") (pintype "passive"))
    )
    (net (code "53") (name "Net-(PCA9533-LED1)") (class "Default")
      (node (ref "PCA9533") (pin "2") (pinfunction "LED1_2") (pintype "bidirectional"))
      (node (ref "R27") (pin "1") (pinfunction "1_1") (pintype "passive"))
    )
    (net (code "54") (name "Net-(PCA9533-LED2)") (class "Default")
      (node (ref "PCA9533") (pin "3") (pinfunction "LED2_3") (pintype "bidirectional"))
      (node (ref "R26") (pin "1") (pinfunction "1_1") (pintype "passive"))
    )
    (net (code "55") (name "Net-(PCA9533-LED3)") (class "Default")
      (node (ref "PCA9533") (pin "5") (pinfunction "LED3_5") (pintype "bidirectional"))
      (node (ref "R16") (pin "1") (pinfunction "1_1") (pintype "passive"))
    )
    (net (code "56") (name "Net-(PI_HEADER-Pad35)") (class "Default")
      (node (ref "PI_HEADER") (pin "35") (pinfunction "35_35") (pintype "passive"))
      (node (ref "SJ4") (pin "2") (pinfunction "2_2") (pintype "passive"))
    )
    (net (code "57") (name "Net-(PI_HEADER-Pad37)") (class "Default")
      (node (ref "PI_HEADER") (pin "37") (pinfunction "37_37") (pintype "passive"))
      (node (ref "SJ3") (pin "2") (pinfunction "2_2") (pintype "passive"))
    )
    (net (code "58") (name "Net-(Q2-B)") (class "Default")
      (node (ref "Q2") (pin "1") (pinfunction "B_1") (pintype "passive"))
      (node (ref "R1") (pin "2") (pinfunction "2_2") (pintype "passive"))
    )
    (net (code "59") (name "Net-(Q4-B)") (class "Default")
      (node (ref "Q4") (pin "1") (pinfunction "B_1") (pintype "passive"))
      (node (ref "R2") (pin "2") (pinfunction "2_2") (pintype "passive"))
    )
    (net (code "60") (name "Net-(Q5-B)") (class "Default")
      (node (ref "Q5") (pin "1") (pinfunction "B_1") (pintype "passive"))
      (node (ref "R5") (pin "2") (pinfunction "2_2") (pintype "passive"))
    )
    (net (code "61") (name "Net-(Q6-B)") (class "Default")
      (node (ref "Q6") (pin "1") (pinfunction "B_1") (pintype "passive"))
      (node (ref "R6") (pin "2") (pinfunction "2_2") (pintype "passive"))
    )
    (net (code "62") (name "Net-(Q7-B)") (class "Default")
      (node (ref "Q7") (pin "1") (pinfunction "B_1") (pintype "passive"))
      (node (ref "R9") (pin "2") (pinfunction "2_2") (pintype "passive"))
    )
    (net (code "63") (name "Net-(Q8-B)") (class "Default")
      (node (ref "Q8") (pin "1") (pinfunction "B_1") (pintype "passive"))
      (node (ref "R13") (pin "2") (pinfunction "2_2") (pintype "passive"))
    )
    (net (code "64") (name "Net-(Q12-2)") (class "Default")
      (node (ref "C37") (pin "2") (pinfunction "2_2") (pintype "passive"))
      (node (ref "Q12") (pin "3") (pinfunction "2_3") (pintype "passive"))
      (node (ref "STM32F103CB") (pin "5") (pinfunction "OSC_IN_5") (pintype "bidirectional"))
    )
    (net (code "65") (name "Net-(RGB_LED-2)") (class "Default")
      (node (ref "R28") (pin "2") (pinfunction "2_2") (pintype "passive"))
      (node (ref "RGB_LED") (pin "P2") (pinfunction "2_P2") (pintype "bidirectional"))
    )
    (net (code "66") (name "Net-(RGB_LED-3)") (class "Default")
      (node (ref "R27") (pin "2") (pinfunction "2_2") (pintype "passive"))
      (node (ref "RGB_LED") (pin "P3") (pinfunction "3_P3") (pintype "bidirectional"))
    )
    (net (code "67") (name "Net-(RGB_LED-4)") (class "Default")
      (node (ref "R26") (pin "2") (pinfunction "2_2") (pintype "passive"))
      (node (ref "RGB_LED") (pin "P4") (pinfunction "4_P4") (pintype "bidirectional"))
    )
    (net (code "68") (name "Net-(STM32F103CB-OSC_OUT)") (class "Default")
      (node (ref "C36") (pin "2") (pinfunction "2_2") (pintype "passive"))
      (node (ref "Q12") (pin "1") (pinfunction "1_1") (pintype "passive"))
      (node (ref "STM32F103CB") (pin "6") (pinfunction "OSC_OUT_6") (pintype "bidirectional"))
    )
    (net (code "69") (name "Net-(STM32F103CB-PC13-TAMPER-RTC)") (class "Default")
      (node (ref "R30") (pin "1") (pinfunction "1_1") (pintype "passive"))
      (node (ref "STM32F103CB") (pin "2") (pinfunction "PC13-TAMPER-RTC_2") (pintype "bidirectional"))
    )
    (net (code "70") (name "Net-(U1-CPOUT)") (class "Default")
      (node (ref "C17") (pin "1") (pinfunction "1_1") (pintype "passive"))
      (node (ref "U1") (pin "20") (pinfunction "CPOUT_20") (pintype "passive"))
    )
    (net (code "71") (name "Net-(U1-REGOUT)") (class "Default")
      (node (ref "C21") (pin "1") (pinfunction "1_1") (pintype "passive"))
      (node (ref "U1") (pin "10") (pinfunction "REGOUT_10") (pintype "passive"))
    )
    (net (code "72") (name "V+") (class "Default")
      (node (ref "C16") (pin "1") (pinfunction "1_1") (pintype "passive"))
      (node (ref "C27") (pin "+") (pinfunction "+_+") (pintype "passive"))
      (node (ref "R17") (pin "2") (pinfunction "2_2") (pintype "passive"))
      (node (ref "R34") (pin "2") (pinfunction "2_2") (pintype "passive"))
      (node (ref "SUPPLY_IN") (pin "2") (pinfunction "2_2") (pintype "passive"))
      (node (ref "SUPPLY_IN1") (pin "2") (pinfunction "2_2") (pintype "passive"))
      (node (ref "U2") (pin "1") (pinfunction "VIN+_1") (pintype "bidirectional"))
    )
    (net (code "73") (name "unconnected-(PCA9306-SCL1-Pad2)") (class "Default")
      (node (ref "PCA9306") (pin "2") (pinfunction "SCL1_2") (pintype "bidirectional"))
    )
    (net (code "74") (name "unconnected-(PCA9306-SDA1-Pad3)") (class "Default")
      (node (ref "PCA9306") (pin "3") (pinfunction "SDA1_3") (pintype "bidirectional"))
    )
    (net (code "75") (name "unconnected-(PI_HEADER-Pad2)") (class "Default")
      (node (ref "PI_HEADER") (pin "2") (pinfunction "2_2") (pintype "passive"))
    )
    (net (code "76") (name "unconnected-(PI_HEADER-Pad3)") (class "Default")
      (node (ref "PI_HEADER") (pin "3") (pinfunction "3_3") (pintype "passive"))
    )
    (net (code "77") (name "unconnected-(PI_HEADER-Pad4)") (class "Default")
      (node (ref "PI_HEADER") (pin "4") (pinfunction "4_4") (pintype "passive"))
    )
    (net (code "78") (name "unconnected-(PI_HEADER-Pad5)") (class "Default")
      (node (ref "PI_HEADER") (pin "5") (pinfunction "5_5") (pintype "passive"))
    )
    (net (code "79") (name "unconnected-(PI_HEADER-Pad6)") (class "Default")
      (node (ref "PI_HEADER") (pin "6") (pinfunction "6_6") (pintype "passive"))
    )
    (net (code "80") (name "unconnected-(PI_HEADER-Pad7)") (class "Default")
      (node (ref "PI_HEADER") (pin "7") (pinfunction "7_7") (pintype "passive"))
    )
    (net (code "81") (name "unconnected-(PI_HEADER-Pad9)") (class "Default")
      (node (ref "PI_HEADER") (pin "9") (pinfunction "9_9") (pintype "passive"))
    )
    (net (code "82") (name "unconnected-(PI_HEADER-Pad10)") (class "Default")
      (node (ref "PI_HEADER") (pin "10") (pinfunction "10_10") (pintype "passive"))
    )
    (net (code "83") (name "unconnected-(PI_HEADER-Pad11)") (class "Default")
      (node (ref "PI_HEADER") (pin "11") (pinfunction "11_11") (pintype "passive"))
    )
    (net (code "84") (name "unconnected-(PI_HEADER-Pad13)") (class "Default")
      (node (ref "PI_HEADER") (pin "13") (pinfunction "13_13") (pintype "passive"))
    )
    (net (code "85") (name "unconnected-(PI_HEADER-Pad14)") (class "Default")
      (node (ref "PI_HEADER") (pin "14") (pinfunction "14_14") (pintype "passive"))
    )
    (net (code "86") (name "unconnected-(PI_HEADER-Pad16)") (class "Default")
      (node (ref "PI_HEADER") (pin "16") (pinfunction "16_16") (pintype "passive"))
    )
    (net (code "87") (name "unconnected-(PI_HEADER-Pad17)") (class "Default")
      (node (ref "PI_HEADER") (pin "17") (pinfunction "17_17") (pintype "passive"))
    )
    (net (code "88") (name "unconnected-(PI_HEADER-Pad18)") (class "Default")
      (node (ref "PI_HEADER") (pin "18") (pinfunction "18_18") (pintype "passive"))
    )
    (net (code "89") (name "unconnected-(PI_HEADER-Pad19)") (class "Default")
      (node (ref "PI_HEADER") (pin "19") (pinfunction "19_19") (pintype "passive"))
    )
    (net (code "90") (name "unconnected-(PI_HEADER-Pad21)") (class "Default")
      (node (ref "PI_HEADER") (pin "21") (pinfunction "21_21") (pintype "passive"))
    )
    (net (code "91") (name "unconnected-(PI_HEADER-Pad23)") (class "Default")
      (node (ref "PI_HEADER") (pin "23") (pinfunction "23_23") (pintype "passive"))
    )
    (net (code "92") (name "unconnected-(PI_HEADER-Pad25)") (class "Default")
      (node (ref "PI_HEADER") (pin "25") (pinfunction "25_25") (pintype "passive"))
    )
    (net (code "93") (name "unconnected-(PI_HEADER-Pad27)") (class "Default")
      (node (ref "PI_HEADER") (pin "27") (pinfunction "27_27") (pintype "passive"))
    )
    (net (code "94") (name "unconnected-(PI_HEADER-Pad29)") (class "Default")
      (node (ref "PI_HEADER") (pin "29") (pinfunction "29_29") (pintype "passive"))
    )
    (net (code "95") (name "unconnected-(PI_HEADER-Pad30)") (class "Default")
      (node (ref "PI_HEADER") (pin "30") (pinfunction "30_30") (pintype "passive"))
    )
    (net (code "96") (name "unconnected-(PI_HEADER-Pad33)") (class "Default")
      (node (ref "PI_HEADER") (pin "33") (pinfunction "33_33") (pintype "passive"))
    )
    (net (code "97") (name "unconnected-(PI_HEADER-Pad39)") (class "Default")
      (node (ref "PI_HEADER") (pin "39") (pinfunction "39_39") (pintype "passive"))
    )
    (net (code "98") (name "unconnected-(SJ3-Pad1)") (class "Default")
      (node (ref "SJ3") (pin "1") (pinfunction "1_1") (pintype "passive"))
    )
    (net (code "99") (name "unconnected-(SJ4-Pad1)") (class "Default")
      (node (ref "SJ4") (pin "1") (pinfunction "1_1") (pintype "passive"))
    )
    (net (code "100") (name "unconnected-(STM32F103CB-PA1-Pad11)") (class "Default")
      (node (ref "STM32F103CB") (pin "11") (pinfunction "PA1_11") (pintype "bidirectional"))
    )
    (net (code "101") (name "unconnected-(STM32F103CB-PA8-Pad29)") (class "Default")
      (node (ref "STM32F103CB") (pin "29") (pinfunction "PA8_29") (pintype "bidirectional"))
    )
    (net (code "102") (name "unconnected-(STM32F103CB-PA15-Pad38)") (class "Default")
      (node (ref "STM32F103CB") (pin "38") (pinfunction "PA15_38") (pintype "bidirectional"))
    )
    (net (code "103") (name "unconnected-(STM32F103CB-PB3-Pad39)") (class "Default")
      (node (ref "STM32F103CB") (pin "39") (pinfunction "PB3_39") (pintype "bidirectional"))
    )
    (net (code "104") (name "unconnected-(STM32F103CB-PB4-Pad40)") (class "Default")
      (node (ref "STM32F103CB") (pin "40") (pinfunction "PB4_40") (pintype "bidirectional"))
    )
    (net (code "105") (name "unconnected-(STM32F103CB-PB5-Pad41)") (class "Default")
      (node (ref "STM32F103CB") (pin "41") (pinfunction "PB5_41") (pintype "bidirectional"))
    )
    (net (code "106") (name "unconnected-(STM32F103CB-PB8-Pad45)") (class "Default")
      (node (ref "STM32F103CB") (pin "45") (pinfunction "PB8_45") (pintype "bidirectional"))
    )
    (net (code "107") (name "unconnected-(STM32F103CB-PB9-Pad46)") (class "Default")
      (node (ref "STM32F103CB") (pin "46") (pinfunction "PB9_46") (pintype "bidirectional"))
    )
    (net (code "108") (name "unconnected-(STM32F103CB-PB10-Pad21)") (class "Default")
      (node (ref "STM32F103CB") (pin "21") (pinfunction "PB10_21") (pintype "bidirectional"))
    )
    (net (code "109") (name "unconnected-(STM32F103CB-PB11-Pad22)") (class "Default")
      (node (ref "STM32F103CB") (pin "22") (pinfunction "PB11_22") (pintype "bidirectional"))
    )
    (net (code "110") (name "unconnected-(STM32F103CB-PB13-Pad26)") (class "Default")
      (node (ref "STM32F103CB") (pin "26") (pinfunction "PB13_26") (pintype "bidirectional"))
    )
    (net (code "111") (name "unconnected-(STM32F103CB-PB14-Pad27)") (class "Default")
      (node (ref "STM32F103CB") (pin "27") (pinfunction "PB14_27") (pintype "bidirectional"))
    )
    (net (code "112") (name "unconnected-(STM32F103CB-PC14-OSC32_IN-Pad3)") (class "Default")
      (node (ref "STM32F103CB") (pin "3") (pinfunction "PC14-OSC32_IN_3") (pintype "bidirectional"))
    )
    (net (code "113") (name "unconnected-(STM32F103CB-PC15-OSC32_OUT-Pad4)") (class "Default")
      (node (ref "STM32F103CB") (pin "4") (pinfunction "PC15-OSC32_OUT_4") (pintype "bidirectional"))
    )
    (net (code "114") (name "unconnected-(U1-AUX_CL-Pad7)") (class "Default")
      (node (ref "U1") (pin "7") (pinfunction "AUX_CL_7") (pintype "input"))
    )
    (net (code "115") (name "unconnected-(U1-AUX_DA-Pad6)") (class "Default")
      (node (ref "U1") (pin "6") (pinfunction "AUX_DA_6") (pintype "bidirectional"))
    )
    (net (code "116") (name "unconnected-(U1-RESV-Pad19)") (class "Default")
      (node (ref "U1") (pin "19") (pinfunction "RESV_19") (pintype "passive"))
    )
    (net (code "117") (name "unconnected-(U1-RESV-Pad21)") (class "Default")
      (node (ref "U1") (pin "21") (pinfunction "RESV_21") (pintype "passive"))
    )
    (net (code "118") (name "unconnected-(U1-RESV-Pad22)") (class "Default")
      (node (ref "U1") (pin "22") (pinfunction "RESV_22") (pintype "passive"))
    )
  )
)
